# drv.net
KiCad netlist of a schematic drawn in Altium Designer
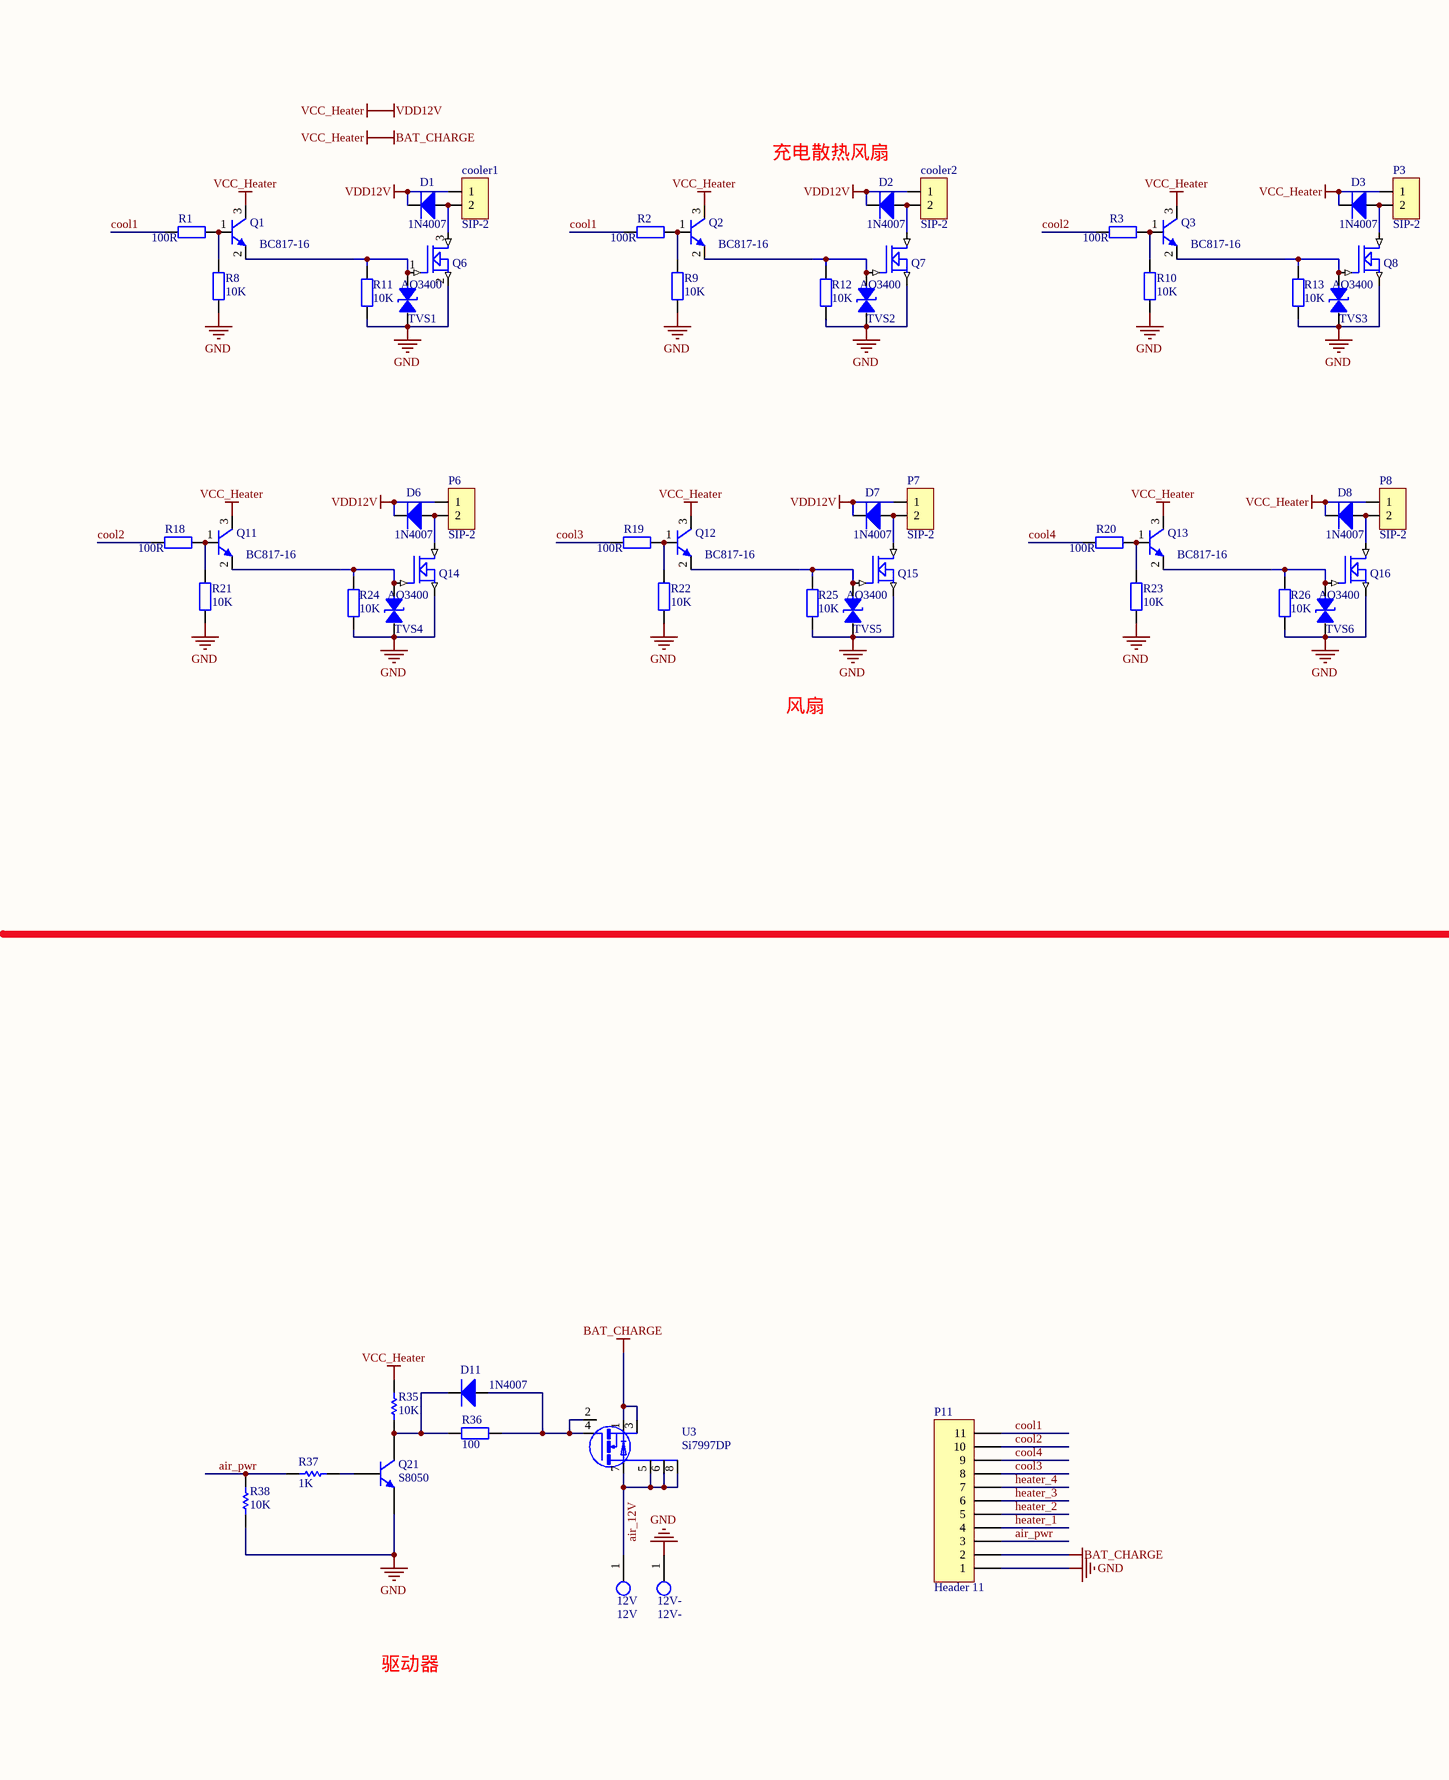
[diagram p0: drv.SchDoc, left]
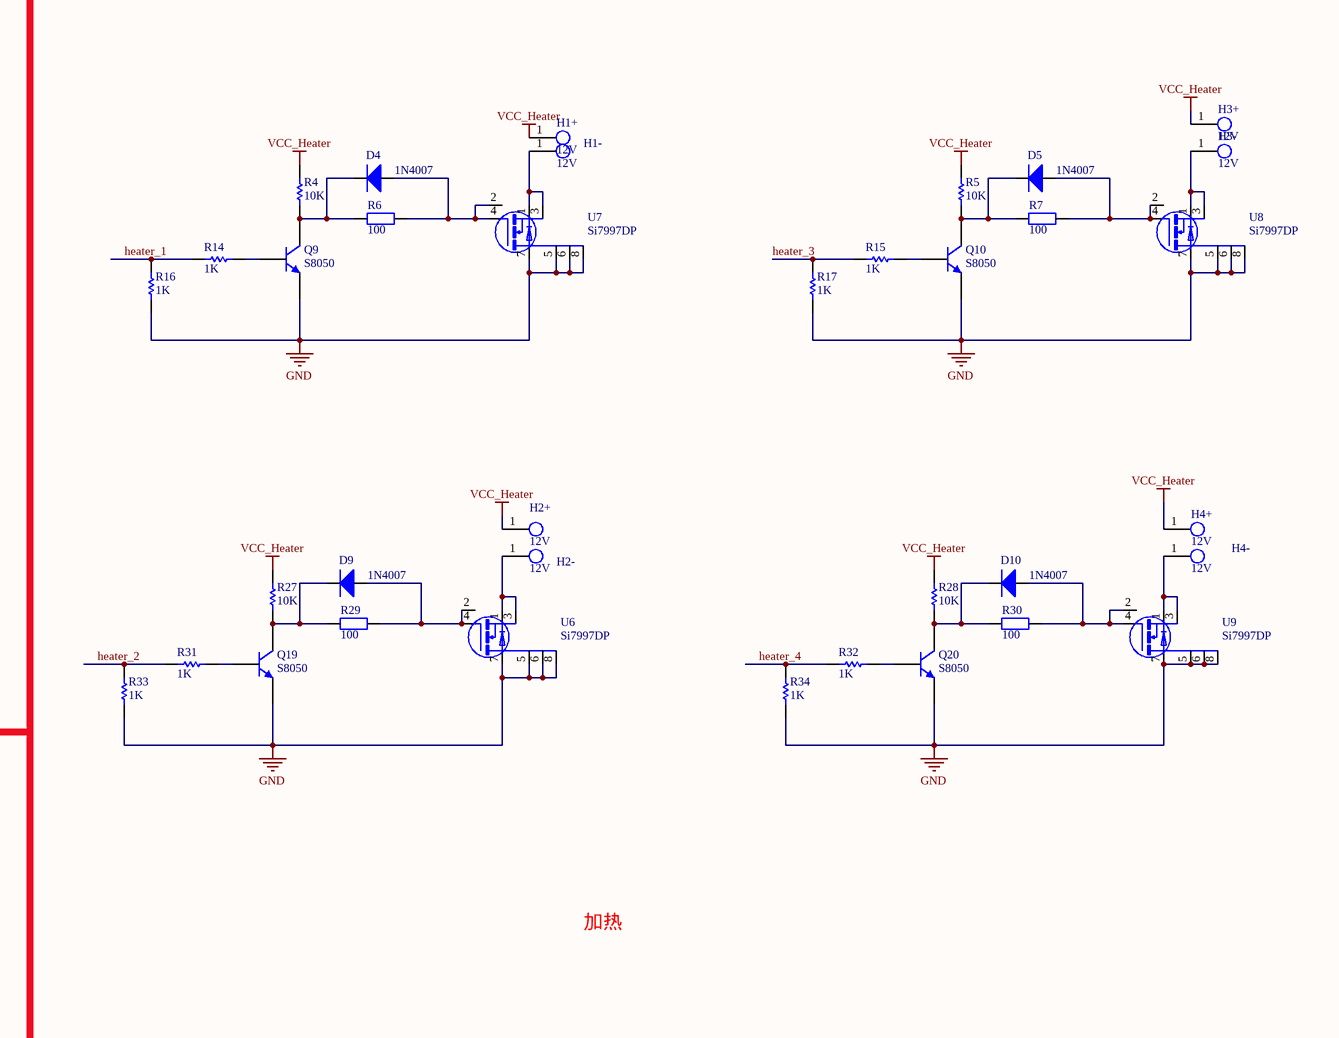
[diagram p1: drv.SchDoc, right]

(export (version "E")
  (design (tool "Eeschema 10.0.6"))
  (components
    (comp (ref "12V") (value "12V") (footprint "FIX-4.5") (libsource (lib "Schlib_20110825") (part "TP")))
    (comp (ref "12V-") (value "12V-") (footprint "FIX-4.5") (libsource (lib "Schlib_20110825") (part "TP")))
    (comp (ref "cooler1")
      (value "SIP-2")
      (footprint "SIP-2A")
      (description "XH2.54 2P 立贴")
      (libsource (lib "XiaoyI") (part "SIP-2"))
    )
    (comp (ref "cooler2")
      (value "SIP-2")
      (footprint "SIP-2A")
      (description "XH2.54 2P 立贴")
      (libsource (lib "XiaoyI") (part "SIP-2"))
    )
    (comp (ref "D1")
      (value "1N4007")
      (footprint "DO-214-AC")
      (description "贴片二极管")
      (libsource (lib "XiaoyI") (part "DIODE2"))
    )
    (comp (ref "D2")
      (value "1N4007")
      (footprint "DO-214-AC")
      (description "贴片二极管")
      (libsource (lib "XiaoyI") (part "DIODE2"))
    )
    (comp (ref "D3")
      (value "1N4007")
      (footprint "DO-214-AC")
      (description "贴片二极管")
      (libsource (lib "XiaoyI") (part "DIODE2"))
    )
    (comp (ref "D4")
      (value "1N4007")
      (footprint "DO-214-AC")
      (description "贴片二极管")
      (libsource (lib "XiaoyI") (part "DIODE2"))
    )
    (comp (ref "D5")
      (value "1N4007")
      (footprint "DO-214-AC")
      (description "贴片二极管")
      (libsource (lib "XiaoyI") (part "DIODE2"))
    )
    (comp (ref "D6")
      (value "1N4007")
      (footprint "DO-214-AC")
      (description "贴片二极管")
      (libsource (lib "XiaoyI") (part "DIODE2"))
    )
    (comp (ref "D7")
      (value "1N4007")
      (footprint "DO-214-AC")
      (description "贴片二极管")
      (libsource (lib "XiaoyI") (part "DIODE2"))
    )
    (comp (ref "D8")
      (value "1N4007")
      (footprint "DO-214-AC")
      (description "贴片二极管")
      (libsource (lib "XiaoyI") (part "DIODE2"))
    )
    (comp (ref "D9")
      (value "1N4007")
      (footprint "DO-214-AC")
      (description "贴片二极管")
      (libsource (lib "XiaoyI") (part "DIODE2"))
    )
    (comp (ref "D10")
      (value "1N4007")
      (footprint "DO-214-AC")
      (description "贴片二极管")
      (libsource (lib "XiaoyI") (part "DIODE2"))
    )
    (comp (ref "D11")
      (value "1N4007")
      (footprint "DO-214-AC")
      (description "贴片二极管")
      (libsource (lib "XiaoyI") (part "DIODE2"))
    )
    (comp (ref "H1+") (value "12V") (footprint "FIX-4.5") (libsource (lib "Schlib_20110825") (part "TP")))
    (comp (ref "H1-") (value "12V") (footprint "FIX-4.5") (libsource (lib "Schlib_20110825") (part "TP")))
    (comp (ref "H2+") (value "12V") (footprint "FIX-4.5") (libsource (lib "Schlib_20110825") (part "TP")))
    (comp (ref "H2-") (value "12V") (footprint "FIX-4.5") (libsource (lib "Schlib_20110825") (part "TP")))
    (comp (ref "H3+") (value "12V") (footprint "FIX-4.5") (libsource (lib "Schlib_20110825") (part "TP")))
    (comp (ref "H3-") (value "12V") (footprint "FIX-4.5") (libsource (lib "Schlib_20110825") (part "TP")))
    (comp (ref "H4+") (value "12V") (footprint "FIX-4.5") (libsource (lib "Schlib_20110825") (part "TP")))
    (comp (ref "H4-") (value "12V") (footprint "FIX-4.5") (libsource (lib "Schlib_20110825") (part "TP")))
    (comp (ref "P3")
      (value "SIP-2")
      (footprint "SIP-2A")
      (description "XH2.54 2P 立贴")
      (libsource (lib "XiaoyI") (part "SIP-2"))
    )
    (comp (ref "P6")
      (value "SIP-2")
      (footprint "SIP-2A")
      (description "XH2.54 2P 立贴")
      (libsource (lib "XiaoyI") (part "SIP-2"))
    )
    (comp (ref "P7")
      (value "SIP-2")
      (footprint "SIP-2A")
      (description "XH2.54 2P 立贴")
      (libsource (lib "XiaoyI") (part "SIP-2"))
    )
    (comp (ref "P8")
      (value "SIP-2")
      (footprint "SIP-2A")
      (description "XH2.54 2P 立贴")
      (libsource (lib "XiaoyI") (part "SIP-2"))
    )
    (comp (ref "P11")
      (value "Header 11")
      (footprint "12X2MMZ")
      (description "Header, 11-Pin")
      (fields (field (name "PUBLISHER") "Altium Limited"))
      (libsource (lib "Miscellaneous Connectors") (part "Header 11"))
    )
    (comp (ref "Q1")
      (value "BC817-16")
      (footprint "SOT23-3")
      (description "三极管")
      (libsource (lib "XiaoyI") (part "NPN-1"))
    )
    (comp (ref "Q2")
      (value "BC817-16")
      (footprint "SOT23-3")
      (description "三极管")
      (libsource (lib "XiaoyI") (part "NPN-1"))
    )
    (comp (ref "Q3")
      (value "BC817-16")
      (footprint "SOT23-3")
      (description "三极管")
      (libsource (lib "XiaoyI") (part "NPN-1"))
    )
    (comp (ref "Q6")
      (value "AO3400")
      (footprint "SOT23-3")
      (description "MOSFET N")
      (libsource (lib "") (part "MOSFET N_1"))
    )
    (comp (ref "Q7")
      (value "AO3400")
      (footprint "SOT23-3")
      (description "MOSFET N")
      (libsource (lib "XiaoyI") (part "MOSFET N"))
    )
    (comp (ref "Q8")
      (value "AO3400")
      (footprint "SOT23-3")
      (description "MOSFET N")
      (libsource (lib "XiaoyI") (part "MOSFET N"))
    )
    (comp (ref "Q9")
      (value "S8050")
      (footprint "SOT23-3")
      (description "NPN Bipolar Transistor")
      (fields (field (name "PUBLISHER") "Altium Limited"))
      (libsource (lib "Miscellaneous Devices") (part "NPN"))
    )
    (comp (ref "Q10")
      (value "S8050")
      (footprint "SOT23-3")
      (description "NPN Bipolar Transistor")
      (fields (field (name "PUBLISHER") "Altium Limited"))
      (libsource (lib "Miscellaneous Devices") (part "NPN"))
    )
    (comp (ref "Q11")
      (value "BC817-16")
      (footprint "SOT23-3")
      (description "三极管")
      (libsource (lib "XiaoyI") (part "NPN-1"))
    )
    (comp (ref "Q12")
      (value "BC817-16")
      (footprint "SOT23-3")
      (description "三极管")
      (libsource (lib "XiaoyI") (part "NPN-1"))
    )
    (comp (ref "Q13")
      (value "BC817-16")
      (footprint "SOT23-3")
      (description "三极管")
      (libsource (lib "XiaoyI") (part "NPN-1"))
    )
    (comp (ref "Q14")
      (value "AO3400")
      (footprint "SOT23-3")
      (description "MOSFET N")
      (libsource (lib "XiaoyI") (part "MOSFET N"))
    )
    (comp (ref "Q15")
      (value "AO3400")
      (footprint "SOT23-3")
      (description "MOSFET N")
      (libsource (lib "XiaoyI") (part "MOSFET N"))
    )
    (comp (ref "Q16")
      (value "AO3400")
      (footprint "SOT23-3")
      (description "MOSFET N")
      (libsource (lib "XiaoyI") (part "MOSFET N"))
    )
    (comp (ref "Q19")
      (value "S8050")
      (footprint "SOT23-3")
      (description "NPN Bipolar Transistor")
      (fields (field (name "PUBLISHER") "Altium Limited"))
      (libsource (lib "Miscellaneous Devices") (part "NPN"))
    )
    (comp (ref "Q20")
      (value "S8050")
      (footprint "SOT23-3")
      (description "NPN Bipolar Transistor")
      (fields (field (name "PUBLISHER") "Altium Limited"))
      (libsource (lib "Miscellaneous Devices") (part "NPN"))
    )
    (comp (ref "Q21")
      (value "S8050")
      (footprint "SOT23-3")
      (description "NPN Bipolar Transistor")
      (fields (field (name "PUBLISHER") "Altium Limited"))
      (libsource (lib "Miscellaneous Devices") (part "NPN"))
    )
    (comp (ref "R1")
      (value "100R")
      (footprint "0603R")
      (description "贴片电阻 5%")
      (libsource (lib "") (part "RES-SOP_1"))
    )
    (comp (ref "R2")
      (value "100R")
      (footprint "0603R")
      (description "贴片电阻 5%")
      (libsource (lib "") (part "RES-SOP_1"))
    )
    (comp (ref "R3")
      (value "100R")
      (footprint "0603R")
      (description "贴片电阻 5%")
      (libsource (lib "") (part "RES-SOP_1"))
    )
    (comp (ref "R4")
      (value "10K")
      (footprint "0603R")
      (description "Resistor")
      (fields (field (name "PUBLISHER") "Altium Limited"))
      (libsource (lib "Miscellaneous Devices") (part "Res1"))
    )
    (comp (ref "R5")
      (value "10K")
      (footprint "0603R")
      (description "Resistor")
      (fields (field (name "PUBLISHER") "Altium Limited"))
      (libsource (lib "Miscellaneous Devices") (part "Res1"))
    )
    (comp (ref "R6")
      (value "100")
      (footprint "0603R")
      (description "贴片电阻 5%")
      (libsource (lib "XiaoyI") (part "RES-SOP"))
    )
    (comp (ref "R7")
      (value "100")
      (footprint "0603R")
      (description "贴片电阻 5%")
      (libsource (lib "XiaoyI") (part "RES-SOP"))
    )
    (comp (ref "R8")
      (value "10K")
      (footprint "0603R")
      (description "贴片电阻 5%")
      (libsource (lib "") (part "RES-SOP_3"))
    )
    (comp (ref "R9")
      (value "10K")
      (footprint "0603R")
      (description "贴片电阻 5%")
      (libsource (lib "") (part "RES-SOP_3"))
    )
    (comp (ref "R10")
      (value "10K")
      (footprint "0603R")
      (description "贴片电阻 5%")
      (libsource (lib "") (part "RES-SOP_3"))
    )
    (comp (ref "R11")
      (value "10K")
      (footprint "0603R")
      (description "贴片电阻 5%")
      (libsource (lib "") (part "RES-SOP_2"))
    )
    (comp (ref "R12")
      (value "10K")
      (footprint "0603R")
      (description "贴片电阻 5%")
      (libsource (lib "") (part "RES-SOP_2"))
    )
    (comp (ref "R13")
      (value "10K")
      (footprint "0603R")
      (description "贴片电阻 5%")
      (libsource (lib "") (part "RES-SOP_2"))
    )
    (comp (ref "R14")
      (value "1K")
      (footprint "0603R")
      (description "Resistor")
      (fields (field (name "PUBLISHER") "Altium Limited"))
      (libsource (lib "Miscellaneous Devices") (part "Res1"))
    )
    (comp (ref "R15")
      (value "1K")
      (footprint "0603R")
      (description "Resistor")
      (fields (field (name "PUBLISHER") "Altium Limited"))
      (libsource (lib "Miscellaneous Devices") (part "Res1"))
    )
    (comp (ref "R16")
      (value "1K")
      (footprint "0603R")
      (description "Resistor")
      (fields (field (name "PUBLISHER") "Altium Limited"))
      (libsource (lib "Miscellaneous Devices") (part "Res1"))
    )
    (comp (ref "R17")
      (value "1K")
      (footprint "0603R")
      (description "Resistor")
      (fields (field (name "PUBLISHER") "Altium Limited"))
      (libsource (lib "Miscellaneous Devices") (part "Res1"))
    )
    (comp (ref "R18")
      (value "100R")
      (footprint "0603R")
      (description "贴片电阻 5%")
      (libsource (lib "") (part "RES-SOP_1"))
    )
    (comp (ref "R19")
      (value "100R")
      (footprint "0603R")
      (description "贴片电阻 5%")
      (libsource (lib "") (part "RES-SOP_1"))
    )
    (comp (ref "R20")
      (value "100R")
      (footprint "0603R")
      (description "贴片电阻 5%")
      (libsource (lib "") (part "RES-SOP_1"))
    )
    (comp (ref "R21")
      (value "10K")
      (footprint "0603R")
      (description "贴片电阻 5%")
      (libsource (lib "") (part "RES-SOP_3"))
    )
    (comp (ref "R22")
      (value "10K")
      (footprint "0603R")
      (description "贴片电阻 5%")
      (libsource (lib "") (part "RES-SOP_3"))
    )
    (comp (ref "R23")
      (value "10K")
      (footprint "0603R")
      (description "贴片电阻 5%")
      (libsource (lib "") (part "RES-SOP_3"))
    )
    (comp (ref "R24")
      (value "10K")
      (footprint "0603R")
      (description "贴片电阻 5%")
      (libsource (lib "") (part "RES-SOP_2"))
    )
    (comp (ref "R25")
      (value "10K")
      (footprint "0603R")
      (description "贴片电阻 5%")
      (libsource (lib "") (part "RES-SOP_2"))
    )
    (comp (ref "R26")
      (value "10K")
      (footprint "0603R")
      (description "贴片电阻 5%")
      (libsource (lib "") (part "RES-SOP_2"))
    )
    (comp (ref "R27")
      (value "10K")
      (footprint "0603R")
      (description "Resistor")
      (fields (field (name "PUBLISHER") "Altium Limited"))
      (libsource (lib "Miscellaneous Devices") (part "Res1"))
    )
    (comp (ref "R28")
      (value "10K")
      (footprint "0603R")
      (description "Resistor")
      (fields (field (name "PUBLISHER") "Altium Limited"))
      (libsource (lib "Miscellaneous Devices") (part "Res1"))
    )
    (comp (ref "R29")
      (value "100")
      (footprint "0603R")
      (description "贴片电阻 5%")
      (libsource (lib "XiaoyI") (part "RES-SOP"))
    )
    (comp (ref "R30")
      (value "100")
      (footprint "0603R")
      (description "贴片电阻 5%")
      (libsource (lib "XiaoyI") (part "RES-SOP"))
    )
    (comp (ref "R31")
      (value "1K")
      (footprint "0603R")
      (description "Resistor")
      (fields (field (name "PUBLISHER") "Altium Limited"))
      (libsource (lib "Miscellaneous Devices") (part "Res1"))
    )
    (comp (ref "R32")
      (value "1K")
      (footprint "0603R")
      (description "Resistor")
      (fields (field (name "PUBLISHER") "Altium Limited"))
      (libsource (lib "Miscellaneous Devices") (part "Res1"))
    )
    (comp (ref "R33")
      (value "1K")
      (footprint "0603R")
      (description "Resistor")
      (fields (field (name "PUBLISHER") "Altium Limited"))
      (libsource (lib "Miscellaneous Devices") (part "Res1"))
    )
    (comp (ref "R34")
      (value "1K")
      (footprint "0603R")
      (description "Resistor")
      (fields (field (name "PUBLISHER") "Altium Limited"))
      (libsource (lib "Miscellaneous Devices") (part "Res1"))
    )
    (comp (ref "R35")
      (value "10K")
      (footprint "0603R")
      (description "Resistor")
      (fields (field (name "PUBLISHER") "Altium Limited"))
      (libsource (lib "Miscellaneous Devices") (part "Res1"))
    )
    (comp (ref "R36")
      (value "100")
      (footprint "0603R")
      (description "贴片电阻 5%")
      (libsource (lib "XiaoyI") (part "RES-SOP"))
    )
    (comp (ref "R37")
      (value "1K")
      (footprint "0603R")
      (description "Resistor")
      (fields (field (name "PUBLISHER") "Altium Limited"))
      (libsource (lib "Miscellaneous Devices") (part "Res1"))
    )
    (comp (ref "R38")
      (value "10K")
      (footprint "0603R")
      (description "Resistor")
      (fields (field (name "PUBLISHER") "Altium Limited"))
      (libsource (lib "Miscellaneous Devices") (part "Res1"))
    )
    (comp (ref "TVS1")
      (value "ESD5Z5.0CT1G")
      (footprint "SOD-523")
      (description "TVS")
      (libsource (lib "XiaoyI") (part "TVS-1"))
    )
    (comp (ref "TVS2")
      (value "ESD5Z5.0CT1G")
      (footprint "SOD-523")
      (description "TVS")
      (libsource (lib "XiaoyI") (part "TVS-1"))
    )
    (comp (ref "TVS3")
      (value "ESD5Z5.0CT1G")
      (footprint "SOD-523")
      (description "TVS")
      (libsource (lib "XiaoyI") (part "TVS-1"))
    )
    (comp (ref "TVS4")
      (value "ESD5Z5.0CT1G")
      (footprint "SOD-523")
      (description "TVS")
      (libsource (lib "XiaoyI") (part "TVS-1"))
    )
    (comp (ref "TVS5")
      (value "ESD5Z5.0CT1G")
      (footprint "SOD-523")
      (description "TVS")
      (libsource (lib "XiaoyI") (part "TVS-1"))
    )
    (comp (ref "TVS6")
      (value "ESD5Z5.0CT1G")
      (footprint "SOD-523")
      (description "TVS")
      (libsource (lib "XiaoyI") (part "TVS-1"))
    )
    (comp (ref "U3")
      (value "Si7997DP")
      (footprint "PowerPAK SO-8")
      (description "Sia430DJ")
      (libsource (lib "Schlib_20110825") (part "Si7997DP"))
    )
    (comp (ref "U6")
      (value "Si7997DP")
      (footprint "PowerPAK SO-8")
      (description "Sia430DJ")
      (libsource (lib "Schlib_20110825") (part "Si7997DP"))
    )
    (comp (ref "U7")
      (value "Si7997DP")
      (footprint "PowerPAK SO-8")
      (description "Sia430DJ")
      (libsource (lib "Schlib_20110825") (part "Si7997DP"))
    )
    (comp (ref "U8")
      (value "Si7997DP")
      (footprint "PowerPAK SO-8")
      (description "Sia430DJ")
      (libsource (lib "Schlib_20110825") (part "Si7997DP"))
    )
    (comp (ref "U9")
      (value "Si7997DP")
      (footprint "PowerPAK SO-8")
      (description "Sia430DJ")
      (libsource (lib "Schlib_20110825") (part "Si7997DP"))
    )
  )
  (nets
    (net (code "1") (name "/air_12V") (class "Default")
      (node (ref "12V") (pin "1") (pintype "passive"))
      (node (ref "U3") (pin "5") (pinfunction "D_5") (pintype "passive"))
      (node (ref "U3") (pin "6") (pinfunction "D_6") (pintype "passive"))
      (node (ref "U3") (pin "7") (pinfunction "D_7") (pintype "passive"))
      (node (ref "U3") (pin "8") (pinfunction "D_8") (pintype "passive"))
    )
    (net (code "2") (name "/air_pwr") (class "Default")
      (node (ref "P11") (pin "3") (pinfunction "3_3") (pintype "passive"))
      (node (ref "R37") (pin "2") (pinfunction "2_2") (pintype "passive"))
      (node (ref "R38") (pin "1") (pinfunction "1_1") (pintype "passive"))
    )
    (net (code "3") (name "/cool1") (class "Default")
      (node (ref "P11") (pin "11") (pinfunction "11_11") (pintype "passive"))
      (node (ref "R1") (pin "2") (pinfunction "2_2") (pintype "passive"))
      (node (ref "R2") (pin "2") (pinfunction "2_2") (pintype "passive"))
    )
    (net (code "4") (name "/cool2") (class "Default")
      (node (ref "P11") (pin "10") (pinfunction "10_10") (pintype "passive"))
      (node (ref "R18") (pin "2") (pinfunction "2_2") (pintype "passive"))
      (node (ref "R3") (pin "2") (pinfunction "2_2") (pintype "passive"))
    )
    (net (code "5") (name "/cool3") (class "Default")
      (node (ref "P11") (pin "8") (pinfunction "8_8") (pintype "passive"))
      (node (ref "R19") (pin "2") (pinfunction "2_2") (pintype "passive"))
    )
    (net (code "6") (name "/cool4") (class "Default")
      (node (ref "P11") (pin "9") (pinfunction "9_9") (pintype "passive"))
      (node (ref "R20") (pin "2") (pinfunction "2_2") (pintype "passive"))
    )
    (net (code "7") (name "/heater_1") (class "Default")
      (node (ref "P11") (pin "4") (pinfunction "4_4") (pintype "passive"))
      (node (ref "R14") (pin "2") (pinfunction "2_2") (pintype "passive"))
      (node (ref "R16") (pin "1") (pinfunction "1_1") (pintype "passive"))
    )
    (net (code "8") (name "/heater_2") (class "Default")
      (node (ref "P11") (pin "5") (pinfunction "5_5") (pintype "passive"))
      (node (ref "R31") (pin "2") (pinfunction "2_2") (pintype "passive"))
      (node (ref "R33") (pin "1") (pinfunction "1_1") (pintype "passive"))
    )
    (net (code "9") (name "/heater_3") (class "Default")
      (node (ref "P11") (pin "6") (pinfunction "6_6") (pintype "passive"))
      (node (ref "R15") (pin "2") (pinfunction "2_2") (pintype "passive"))
      (node (ref "R17") (pin "1") (pinfunction "1_1") (pintype "passive"))
    )
    (net (code "10") (name "/heater_4") (class "Default")
      (node (ref "P11") (pin "7") (pinfunction "7_7") (pintype "passive"))
      (node (ref "R32") (pin "2") (pinfunction "2_2") (pintype "passive"))
      (node (ref "R34") (pin "1") (pinfunction "1_1") (pintype "passive"))
    )
    (net (code "11") (name "BAT_CHARGE") (class "Default")
      (node (ref "D1") (pin "2") (pinfunction "K_2") (pintype "passive"))
      (node (ref "D2") (pin "2") (pinfunction "K_2") (pintype "passive"))
      (node (ref "D3") (pin "2") (pinfunction "K_2") (pintype "passive"))
      (node (ref "D6") (pin "2") (pinfunction "K_2") (pintype "passive"))
      (node (ref "D7") (pin "2") (pinfunction "K_2") (pintype "passive"))
      (node (ref "D8") (pin "2") (pinfunction "K_2") (pintype "passive"))
      (node (ref "H1+") (pin "1") (pintype "passive"))
      (node (ref "H2+") (pin "1") (pintype "passive"))
      (node (ref "H3+") (pin "1") (pintype "passive"))
      (node (ref "H4+") (pin "1") (pintype "passive"))
      (node (ref "P11") (pin "2") (pinfunction "2_2") (pintype "passive"))
      (node (ref "P3") (pin "1") (pinfunction "1_1") (pintype "passive"))
      (node (ref "P6") (pin "1") (pinfunction "1_1") (pintype "passive"))
      (node (ref "P7") (pin "1") (pinfunction "1_1") (pintype "passive"))
      (node (ref "P8") (pin "1") (pinfunction "1_1") (pintype "passive"))
      (node (ref "Q1") (pin "3") (pinfunction "C_3") (pintype "passive"))
      (node (ref "Q11") (pin "3") (pinfunction "C_3") (pintype "passive"))
      (node (ref "Q12") (pin "3") (pinfunction "C_3") (pintype "passive"))
      (node (ref "Q13") (pin "3") (pinfunction "C_3") (pintype "passive"))
      (node (ref "Q2") (pin "3") (pinfunction "C_3") (pintype "passive"))
      (node (ref "Q3") (pin "3") (pinfunction "C_3") (pintype "passive"))
      (node (ref "R27") (pin "2") (pinfunction "2_2") (pintype "passive"))
      (node (ref "R28") (pin "2") (pinfunction "2_2") (pintype "passive"))
      (node (ref "R35") (pin "2") (pinfunction "2_2") (pintype "passive"))
      (node (ref "R4") (pin "2") (pinfunction "2_2") (pintype "passive"))
      (node (ref "R5") (pin "2") (pinfunction "2_2") (pintype "passive"))
      (node (ref "U3") (pin "1") (pinfunction "S_1") (pintype "passive"))
      (node (ref "U3") (pin "3") (pinfunction "S_3") (pintype "passive"))
      (node (ref "cooler1") (pin "1") (pinfunction "1_1") (pintype "passive"))
      (node (ref "cooler2") (pin "1") (pinfunction "1_1") (pintype "passive"))
    )
    (net (code "12") (name "GND") (class "Default")
      (node (ref "12V-") (pin "1") (pintype "passive"))
      (node (ref "P11") (pin "1") (pinfunction "1_1") (pintype "passive"))
      (node (ref "Q10") (pin "2") (pinfunction "E_2") (pintype "passive"))
      (node (ref "Q14") (pin "2") (pinfunction "S_2") (pintype "output"))
      (node (ref "Q15") (pin "2") (pinfunction "S_2") (pintype "output"))
      (node (ref "Q16") (pin "2") (pinfunction "S_2") (pintype "output"))
      (node (ref "Q19") (pin "2") (pinfunction "E_2") (pintype "passive"))
      (node (ref "Q20") (pin "2") (pinfunction "E_2") (pintype "passive"))
      (node (ref "Q21") (pin "2") (pinfunction "E_2") (pintype "passive"))
      (node (ref "Q6") (pin "2") (pinfunction "S_2") (pintype "output"))
      (node (ref "Q7") (pin "2") (pinfunction "S_2") (pintype "output"))
      (node (ref "Q8") (pin "2") (pinfunction "S_2") (pintype "output"))
      (node (ref "Q9") (pin "2") (pinfunction "E_2") (pintype "passive"))
      (node (ref "R10") (pin "1") (pinfunction "1_1") (pintype "passive"))
      (node (ref "R11") (pin "2") (pinfunction "2_2") (pintype "passive"))
      (node (ref "R12") (pin "2") (pinfunction "2_2") (pintype "passive"))
      (node (ref "R13") (pin "2") (pinfunction "2_2") (pintype "passive"))
      (node (ref "R16") (pin "2") (pinfunction "2_2") (pintype "passive"))
      (node (ref "R17") (pin "2") (pinfunction "2_2") (pintype "passive"))
      (node (ref "R21") (pin "1") (pinfunction "1_1") (pintype "passive"))
      (node (ref "R22") (pin "1") (pinfunction "1_1") (pintype "passive"))
      (node (ref "R23") (pin "1") (pinfunction "1_1") (pintype "passive"))
      (node (ref "R24") (pin "2") (pinfunction "2_2") (pintype "passive"))
      (node (ref "R25") (pin "2") (pinfunction "2_2") (pintype "passive"))
      (node (ref "R26") (pin "2") (pinfunction "2_2") (pintype "passive"))
      (node (ref "R33") (pin "2") (pinfunction "2_2") (pintype "passive"))
      (node (ref "R34") (pin "2") (pinfunction "2_2") (pintype "passive"))
      (node (ref "R38") (pin "2") (pinfunction "2_2") (pintype "passive"))
      (node (ref "R8") (pin "1") (pinfunction "1_1") (pintype "passive"))
      (node (ref "R9") (pin "1") (pinfunction "1_1") (pintype "passive"))
      (node (ref "TVS1") (pin "1") (pinfunction "A_1") (pintype "passive"))
      (node (ref "TVS2") (pin "1") (pinfunction "A_1") (pintype "passive"))
      (node (ref "TVS3") (pin "1") (pinfunction "A_1") (pintype "passive"))
      (node (ref "TVS4") (pin "1") (pinfunction "A_1") (pintype "passive"))
      (node (ref "TVS5") (pin "1") (pinfunction "A_1") (pintype "passive"))
      (node (ref "TVS6") (pin "1") (pinfunction "A_1") (pintype "passive"))
      (node (ref "U6") (pin "5") (pinfunction "D_5") (pintype "passive"))
      (node (ref "U6") (pin "6") (pinfunction "D_6") (pintype "passive"))
      (node (ref "U6") (pin "7") (pinfunction "D_7") (pintype "passive"))
      (node (ref "U6") (pin "8") (pinfunction "D_8") (pintype "passive"))
      (node (ref "U7") (pin "5") (pinfunction "D_5") (pintype "passive"))
      (node (ref "U7") (pin "6") (pinfunction "D_6") (pintype "passive"))
      (node (ref "U7") (pin "7") (pinfunction "D_7") (pintype "passive"))
      (node (ref "U7") (pin "8") (pinfunction "D_8") (pintype "passive"))
      (node (ref "U8") (pin "5") (pinfunction "D_5") (pintype "passive"))
      (node (ref "U8") (pin "6") (pinfunction "D_6") (pintype "passive"))
      (node (ref "U8") (pin "7") (pinfunction "D_7") (pintype "passive"))
      (node (ref "U8") (pin "8") (pinfunction "D_8") (pintype "passive"))
      (node (ref "U9") (pin "5") (pinfunction "D_5") (pintype "passive"))
      (node (ref "U9") (pin "6") (pinfunction "D_6") (pintype "passive"))
      (node (ref "U9") (pin "7") (pinfunction "D_7") (pintype "passive"))
      (node (ref "U9") (pin "8") (pinfunction "D_8") (pintype "passive"))
    )
    (net (code "13") (name "Net-(D1-A)") (class "Default")
      (node (ref "D1") (pin "1") (pinfunction "A_1") (pintype "passive"))
      (node (ref "Q6") (pin "3") (pinfunction "D_3") (pintype "input"))
      (node (ref "cooler1") (pin "2") (pinfunction "2_2") (pintype "passive"))
    )
    (net (code "14") (name "Net-(D2-A)") (class "Default")
      (node (ref "D2") (pin "1") (pinfunction "A_1") (pintype "passive"))
      (node (ref "Q7") (pin "3") (pinfunction "D_3") (pintype "input"))
      (node (ref "cooler2") (pin "2") (pinfunction "2_2") (pintype "passive"))
    )
    (net (code "15") (name "Net-(D3-A)") (class "Default")
      (node (ref "D3") (pin "1") (pinfunction "A_1") (pintype "passive"))
      (node (ref "P3") (pin "2") (pinfunction "2_2") (pintype "passive"))
      (node (ref "Q8") (pin "3") (pinfunction "D_3") (pintype "input"))
    )
    (net (code "16") (name "Net-(D4-A)") (class "Default")
      (node (ref "D4") (pin "1") (pinfunction "A_1") (pintype "passive"))
      (node (ref "R6") (pin "2") (pinfunction "2_2") (pintype "passive"))
      (node (ref "U7") (pin "2") (pinfunction "G_2") (pintype "passive"))
      (node (ref "U7") (pin "4") (pinfunction "G_4") (pintype "passive"))
    )
    (net (code "17") (name "Net-(D4-K)") (class "Default")
      (node (ref "D4") (pin "2") (pinfunction "K_2") (pintype "passive"))
      (node (ref "Q9") (pin "3") (pinfunction "C_3") (pintype "passive"))
      (node (ref "R4") (pin "1") (pinfunction "1_1") (pintype "passive"))
      (node (ref "R6") (pin "1") (pinfunction "1_1") (pintype "passive"))
    )
    (net (code "18") (name "Net-(D5-A)") (class "Default")
      (node (ref "D5") (pin "1") (pinfunction "A_1") (pintype "passive"))
      (node (ref "R7") (pin "2") (pinfunction "2_2") (pintype "passive"))
      (node (ref "U8") (pin "2") (pinfunction "G_2") (pintype "passive"))
      (node (ref "U8") (pin "4") (pinfunction "G_4") (pintype "passive"))
    )
    (net (code "19") (name "Net-(D5-K)") (class "Default")
      (node (ref "D5") (pin "2") (pinfunction "K_2") (pintype "passive"))
      (node (ref "Q10") (pin "3") (pinfunction "C_3") (pintype "passive"))
      (node (ref "R5") (pin "1") (pinfunction "1_1") (pintype "passive"))
      (node (ref "R7") (pin "1") (pinfunction "1_1") (pintype "passive"))
    )
    (net (code "20") (name "Net-(D6-A)") (class "Default")
      (node (ref "D6") (pin "1") (pinfunction "A_1") (pintype "passive"))
      (node (ref "P6") (pin "2") (pinfunction "2_2") (pintype "passive"))
      (node (ref "Q14") (pin "3") (pinfunction "D_3") (pintype "input"))
    )
    (net (code "21") (name "Net-(D7-A)") (class "Default")
      (node (ref "D7") (pin "1") (pinfunction "A_1") (pintype "passive"))
      (node (ref "P7") (pin "2") (pinfunction "2_2") (pintype "passive"))
      (node (ref "Q15") (pin "3") (pinfunction "D_3") (pintype "input"))
    )
    (net (code "22") (name "Net-(D8-A)") (class "Default")
      (node (ref "D8") (pin "1") (pinfunction "A_1") (pintype "passive"))
      (node (ref "P8") (pin "2") (pinfunction "2_2") (pintype "passive"))
      (node (ref "Q16") (pin "3") (pinfunction "D_3") (pintype "input"))
    )
    (net (code "23") (name "Net-(D9-A)") (class "Default")
      (node (ref "D9") (pin "1") (pinfunction "A_1") (pintype "passive"))
      (node (ref "R29") (pin "2") (pinfunction "2_2") (pintype "passive"))
      (node (ref "U6") (pin "2") (pinfunction "G_2") (pintype "passive"))
      (node (ref "U6") (pin "4") (pinfunction "G_4") (pintype "passive"))
    )
    (net (code "24") (name "Net-(D9-K)") (class "Default")
      (node (ref "D9") (pin "2") (pinfunction "K_2") (pintype "passive"))
      (node (ref "Q19") (pin "3") (pinfunction "C_3") (pintype "passive"))
      (node (ref "R27") (pin "1") (pinfunction "1_1") (pintype "passive"))
      (node (ref "R29") (pin "1") (pinfunction "1_1") (pintype "passive"))
    )
    (net (code "25") (name "Net-(D10-A)") (class "Default")
      (node (ref "D10") (pin "1") (pinfunction "A_1") (pintype "passive"))
      (node (ref "R30") (pin "2") (pinfunction "2_2") (pintype "passive"))
      (node (ref "U9") (pin "2") (pinfunction "G_2") (pintype "passive"))
      (node (ref "U9") (pin "4") (pinfunction "G_4") (pintype "passive"))
    )
    (net (code "26") (name "Net-(D10-K)") (class "Default")
      (node (ref "D10") (pin "2") (pinfunction "K_2") (pintype "passive"))
      (node (ref "Q20") (pin "3") (pinfunction "C_3") (pintype "passive"))
      (node (ref "R28") (pin "1") (pinfunction "1_1") (pintype "passive"))
      (node (ref "R30") (pin "1") (pinfunction "1_1") (pintype "passive"))
    )
    (net (code "27") (name "Net-(D11-A)") (class "Default")
      (node (ref "D11") (pin "1") (pinfunction "A_1") (pintype "passive"))
      (node (ref "R36") (pin "2") (pinfunction "2_2") (pintype "passive"))
      (node (ref "U3") (pin "2") (pinfunction "G_2") (pintype "passive"))
      (node (ref "U3") (pin "4") (pinfunction "G_4") (pintype "passive"))
    )
    (net (code "28") (name "Net-(D11-K)") (class "Default")
      (node (ref "D11") (pin "2") (pinfunction "K_2") (pintype "passive"))
      (node (ref "Q21") (pin "3") (pinfunction "C_3") (pintype "passive"))
      (node (ref "R35") (pin "1") (pinfunction "1_1") (pintype "passive"))
      (node (ref "R36") (pin "1") (pinfunction "1_1") (pintype "passive"))
    )
    (net (code "29") (name "Net-(H1--Pad1)") (class "Default")
      (node (ref "H1-") (pin "1") (pintype "passive"))
      (node (ref "U7") (pin "1") (pinfunction "S_1") (pintype "passive"))
      (node (ref "U7") (pin "3") (pinfunction "S_3") (pintype "passive"))
    )
    (net (code "30") (name "Net-(H2--Pad1)") (class "Default")
      (node (ref "H2-") (pin "1") (pintype "passive"))
      (node (ref "U6") (pin "1") (pinfunction "S_1") (pintype "passive"))
      (node (ref "U6") (pin "3") (pinfunction "S_3") (pintype "passive"))
    )
    (net (code "31") (name "Net-(H3--Pad1)") (class "Default")
      (node (ref "H3-") (pin "1") (pintype "passive"))
      (node (ref "U8") (pin "1") (pinfunction "S_1") (pintype "passive"))
      (node (ref "U8") (pin "3") (pinfunction "S_3") (pintype "passive"))
    )
    (net (code "32") (name "Net-(H4--Pad1)") (class "Default")
      (node (ref "H4-") (pin "1") (pintype "passive"))
      (node (ref "U9") (pin "1") (pinfunction "S_1") (pintype "passive"))
      (node (ref "U9") (pin "3") (pinfunction "S_3") (pintype "passive"))
    )
    (net (code "33") (name "Net-(Q1-B)") (class "Default")
      (node (ref "Q1") (pin "1") (pinfunction "B_1") (pintype "passive"))
      (node (ref "R1") (pin "1") (pinfunction "1_1") (pintype "passive"))
      (node (ref "R8") (pin "2") (pinfunction "2_2") (pintype "passive"))
    )
    (net (code "34") (name "Net-(Q1-E)") (class "Default")
      (node (ref "Q1") (pin "2") (pinfunction "E_2") (pintype "passive"))
      (node (ref "Q6") (pin "1") (pinfunction "G_1") (pintype "input"))
      (node (ref "R11") (pin "1") (pinfunction "1_1") (pintype "passive"))
      (node (ref "TVS1") (pin "2") (pinfunction "B_2") (pintype "passive"))
    )
    (net (code "35") (name "Net-(Q2-B)") (class "Default")
      (node (ref "Q2") (pin "1") (pinfunction "B_1") (pintype "passive"))
      (node (ref "R2") (pin "1") (pinfunction "1_1") (pintype "passive"))
      (node (ref "R9") (pin "2") (pinfunction "2_2") (pintype "passive"))
    )
    (net (code "36") (name "Net-(Q2-E)") (class "Default")
      (node (ref "Q2") (pin "2") (pinfunction "E_2") (pintype "passive"))
      (node (ref "Q7") (pin "1") (pinfunction "G_1") (pintype "input"))
      (node (ref "R12") (pin "1") (pinfunction "1_1") (pintype "passive"))
      (node (ref "TVS2") (pin "2") (pinfunction "B_2") (pintype "passive"))
    )
    (net (code "37") (name "Net-(Q3-B)") (class "Default")
      (node (ref "Q3") (pin "1") (pinfunction "B_1") (pintype "passive"))
      (node (ref "R10") (pin "2") (pinfunction "2_2") (pintype "passive"))
      (node (ref "R3") (pin "1") (pinfunction "1_1") (pintype "passive"))
    )
    (net (code "38") (name "Net-(Q3-E)") (class "Default")
      (node (ref "Q3") (pin "2") (pinfunction "E_2") (pintype "passive"))
      (node (ref "Q8") (pin "1") (pinfunction "G_1") (pintype "input"))
      (node (ref "R13") (pin "1") (pinfunction "1_1") (pintype "passive"))
      (node (ref "TVS3") (pin "2") (pinfunction "B_2") (pintype "passive"))
    )
    (net (code "39") (name "Net-(Q9-B)") (class "Default")
      (node (ref "Q9") (pin "1") (pinfunction "B_1") (pintype "passive"))
      (node (ref "R14") (pin "1") (pinfunction "1_1") (pintype "passive"))
    )
    (net (code "40") (name "Net-(Q10-B)") (class "Default")
      (node (ref "Q10") (pin "1") (pinfunction "B_1") (pintype "passive"))
      (node (ref "R15") (pin "1") (pinfunction "1_1") (pintype "passive"))
    )
    (net (code "41") (name "Net-(Q11-B)") (class "Default")
      (node (ref "Q11") (pin "1") (pinfunction "B_1") (pintype "passive"))
      (node (ref "R18") (pin "1") (pinfunction "1_1") (pintype "passive"))
      (node (ref "R21") (pin "2") (pinfunction "2_2") (pintype "passive"))
    )
    (net (code "42") (name "Net-(Q11-E)") (class "Default")
      (node (ref "Q11") (pin "2") (pinfunction "E_2") (pintype "passive"))
      (node (ref "Q14") (pin "1") (pinfunction "G_1") (pintype "input"))
      (node (ref "R24") (pin "1") (pinfunction "1_1") (pintype "passive"))
      (node (ref "TVS4") (pin "2") (pinfunction "B_2") (pintype "passive"))
    )
    (net (code "43") (name "Net-(Q12-B)") (class "Default")
      (node (ref "Q12") (pin "1") (pinfunction "B_1") (pintype "passive"))
      (node (ref "R19") (pin "1") (pinfunction "1_1") (pintype "passive"))
      (node (ref "R22") (pin "2") (pinfunction "2_2") (pintype "passive"))
    )
    (net (code "44") (name "Net-(Q12-E)") (class "Default")
      (node (ref "Q12") (pin "2") (pinfunction "E_2") (pintype "passive"))
      (node (ref "Q15") (pin "1") (pinfunction "G_1") (pintype "input"))
      (node (ref "R25") (pin "1") (pinfunction "1_1") (pintype "passive"))
      (node (ref "TVS5") (pin "2") (pinfunction "B_2") (pintype "passive"))
    )
    (net (code "45") (name "Net-(Q13-B)") (class "Default")
      (node (ref "Q13") (pin "1") (pinfunction "B_1") (pintype "passive"))
      (node (ref "R20") (pin "1") (pinfunction "1_1") (pintype "passive"))
      (node (ref "R23") (pin "2") (pinfunction "2_2") (pintype "passive"))
    )
    (net (code "46") (name "Net-(Q13-E)") (class "Default")
      (node (ref "Q13") (pin "2") (pinfunction "E_2") (pintype "passive"))
      (node (ref "Q16") (pin "1") (pinfunction "G_1") (pintype "input"))
      (node (ref "R26") (pin "1") (pinfunction "1_1") (pintype "passive"))
      (node (ref "TVS6") (pin "2") (pinfunction "B_2") (pintype "passive"))
    )
    (net (code "47") (name "Net-(Q19-B)") (class "Default")
      (node (ref "Q19") (pin "1") (pinfunction "B_1") (pintype "passive"))
      (node (ref "R31") (pin "1") (pinfunction "1_1") (pintype "passive"))
    )
    (net (code "48") (name "Net-(Q20-B)") (class "Default")
      (node (ref "Q20") (pin "1") (pinfunction "B_1") (pintype "passive"))
      (node (ref "R32") (pin "1") (pinfunction "1_1") (pintype "passive"))
    )
    (net (code "49") (name "Net-(Q21-B)") (class "Default")
      (node (ref "Q21") (pin "1") (pinfunction "B_1") (pintype "passive"))
      (node (ref "R37") (pin "1") (pinfunction "1_1") (pintype "passive"))
    )
  )
)
